# 0273_GPU_STRAPS-2.net
KiCad netlist of a schematic drawn in Altium Designer
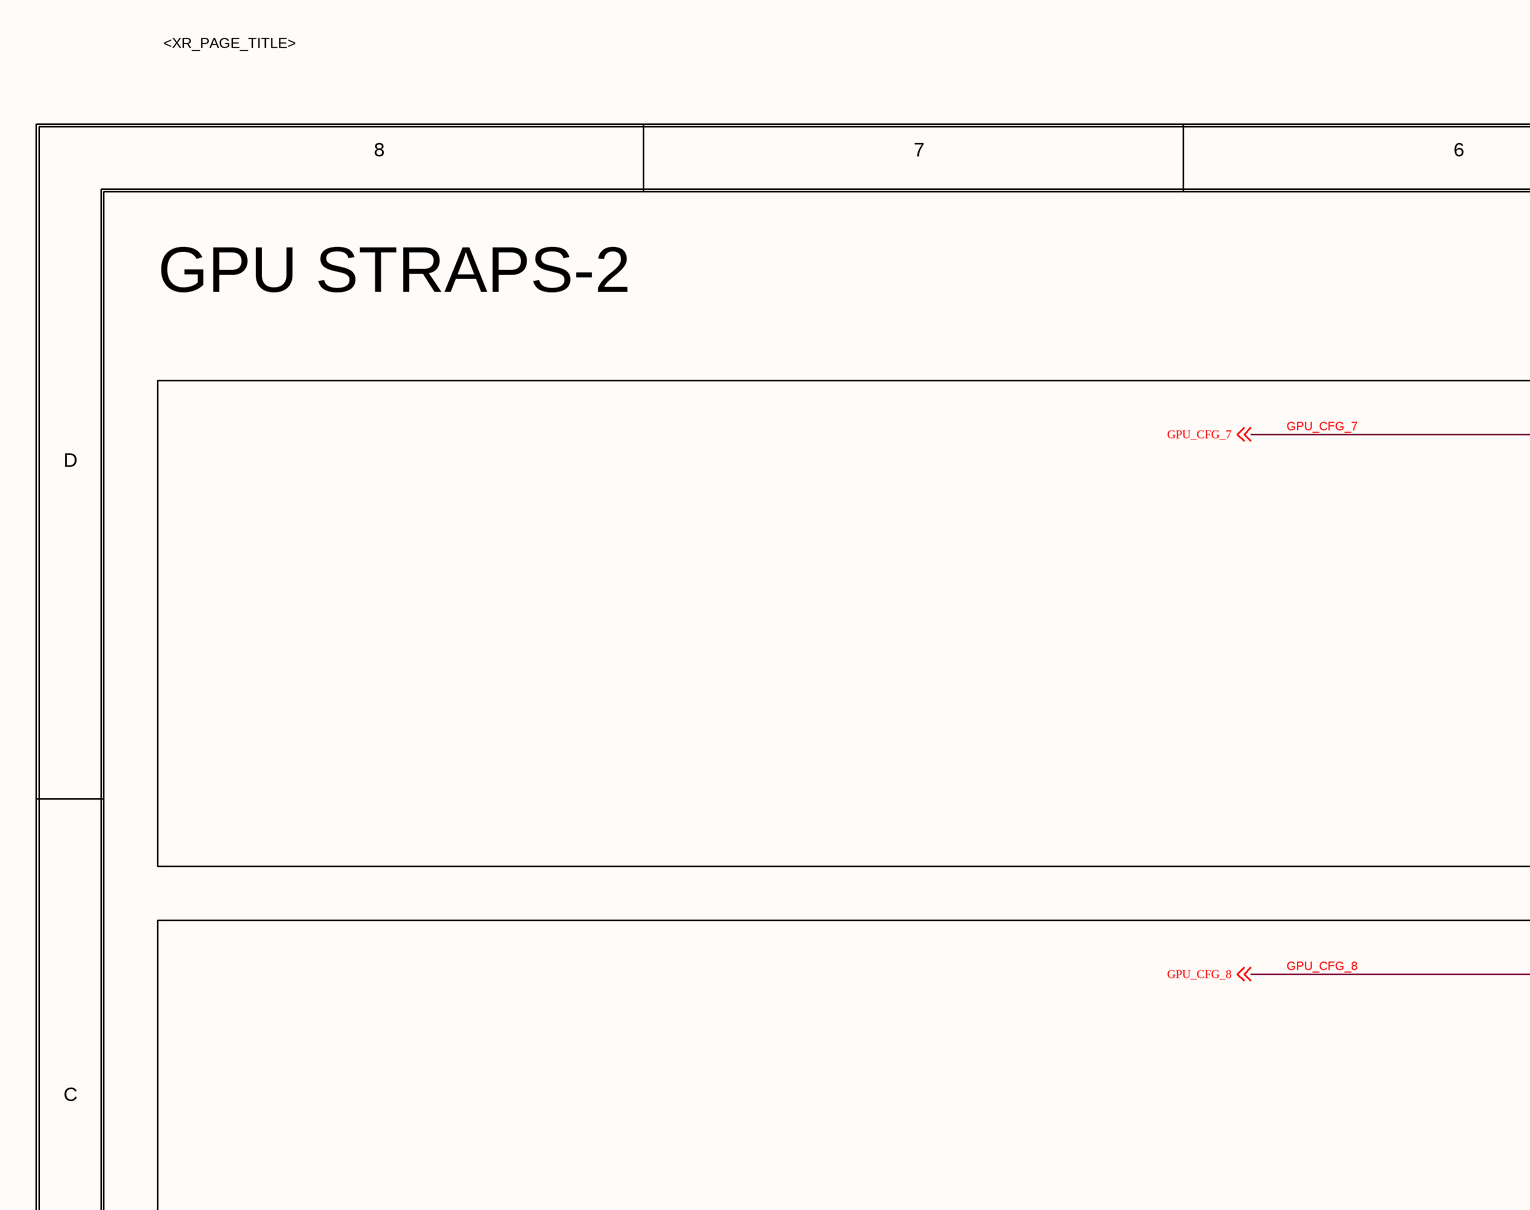
[diagram p0: 0273_GPU STRAPS-2.SchDoc, top left]
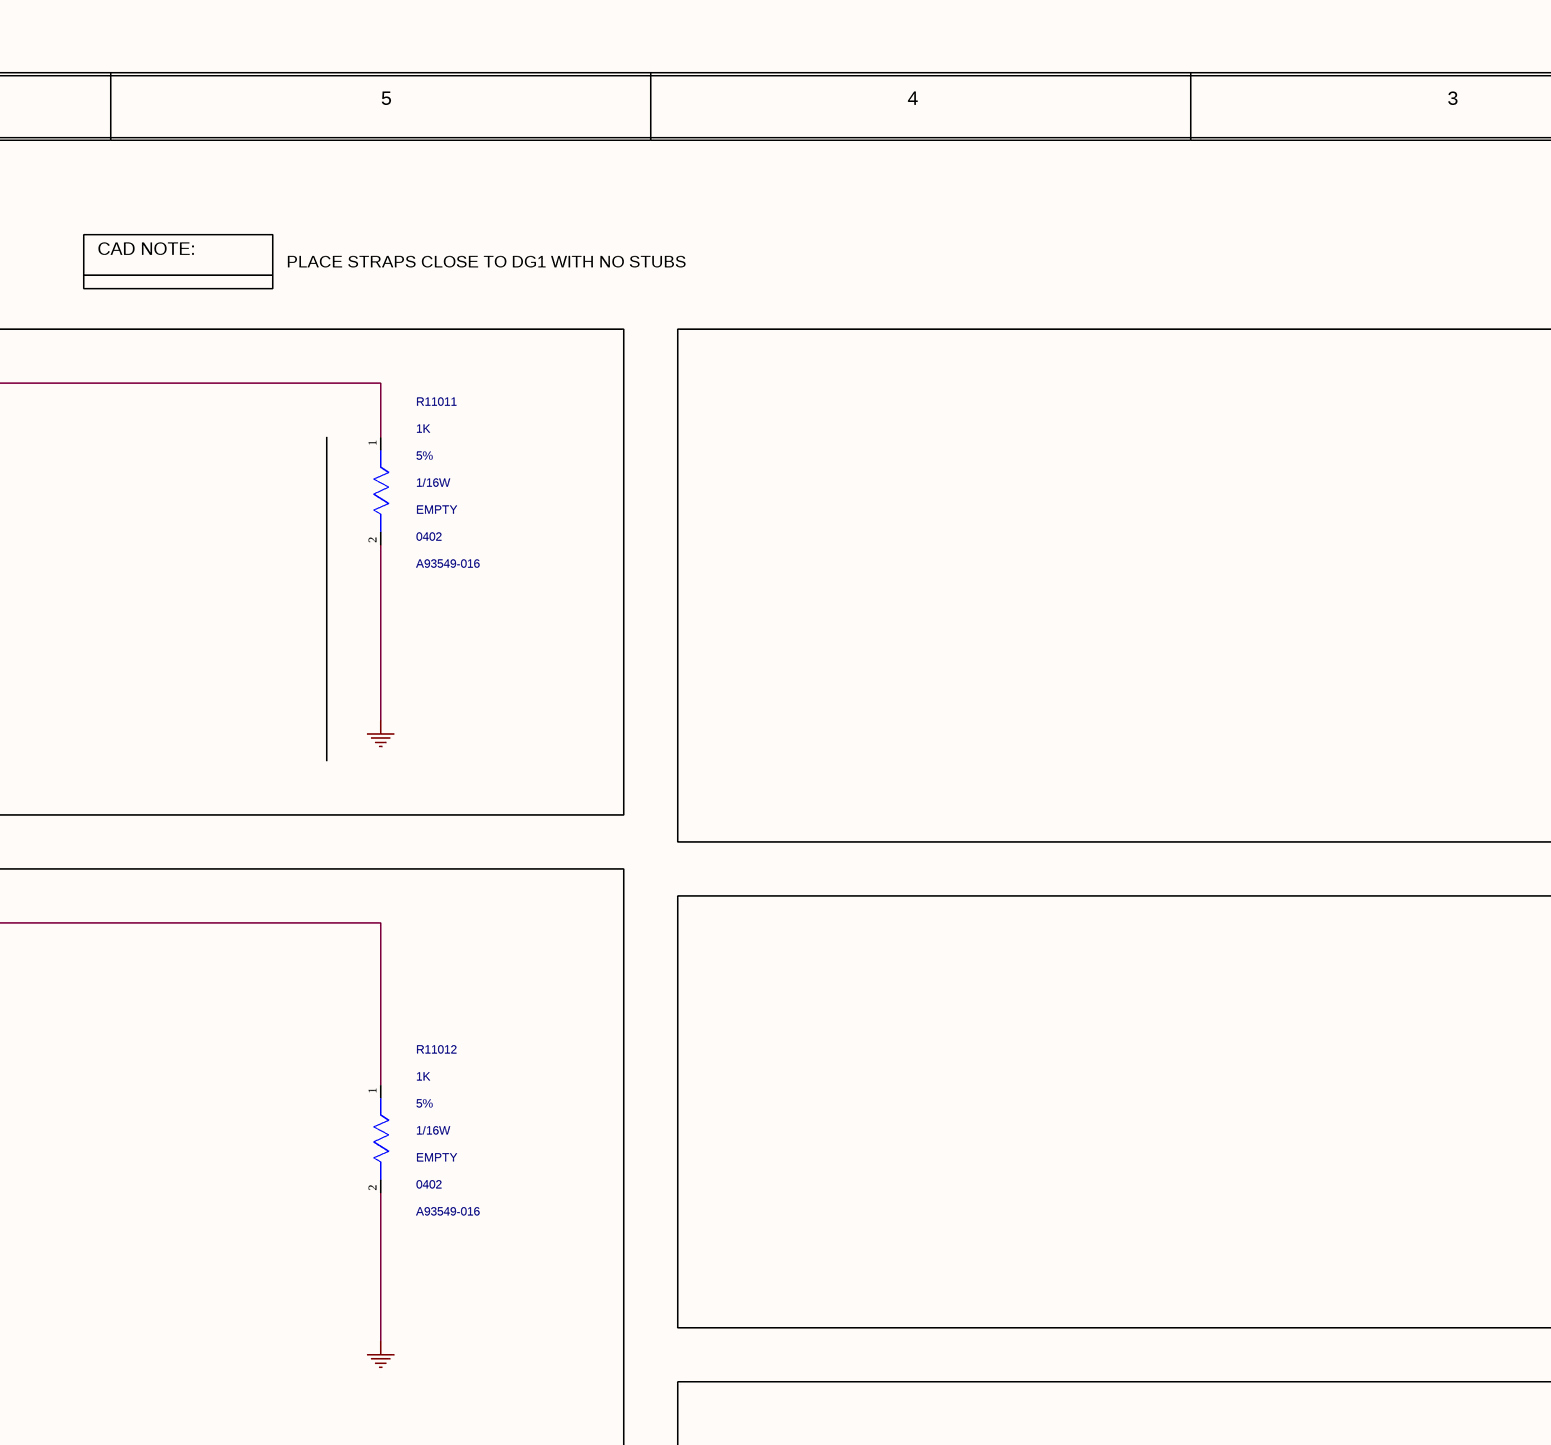
[diagram p1: 0273_GPU STRAPS-2.SchDoc, top middle]
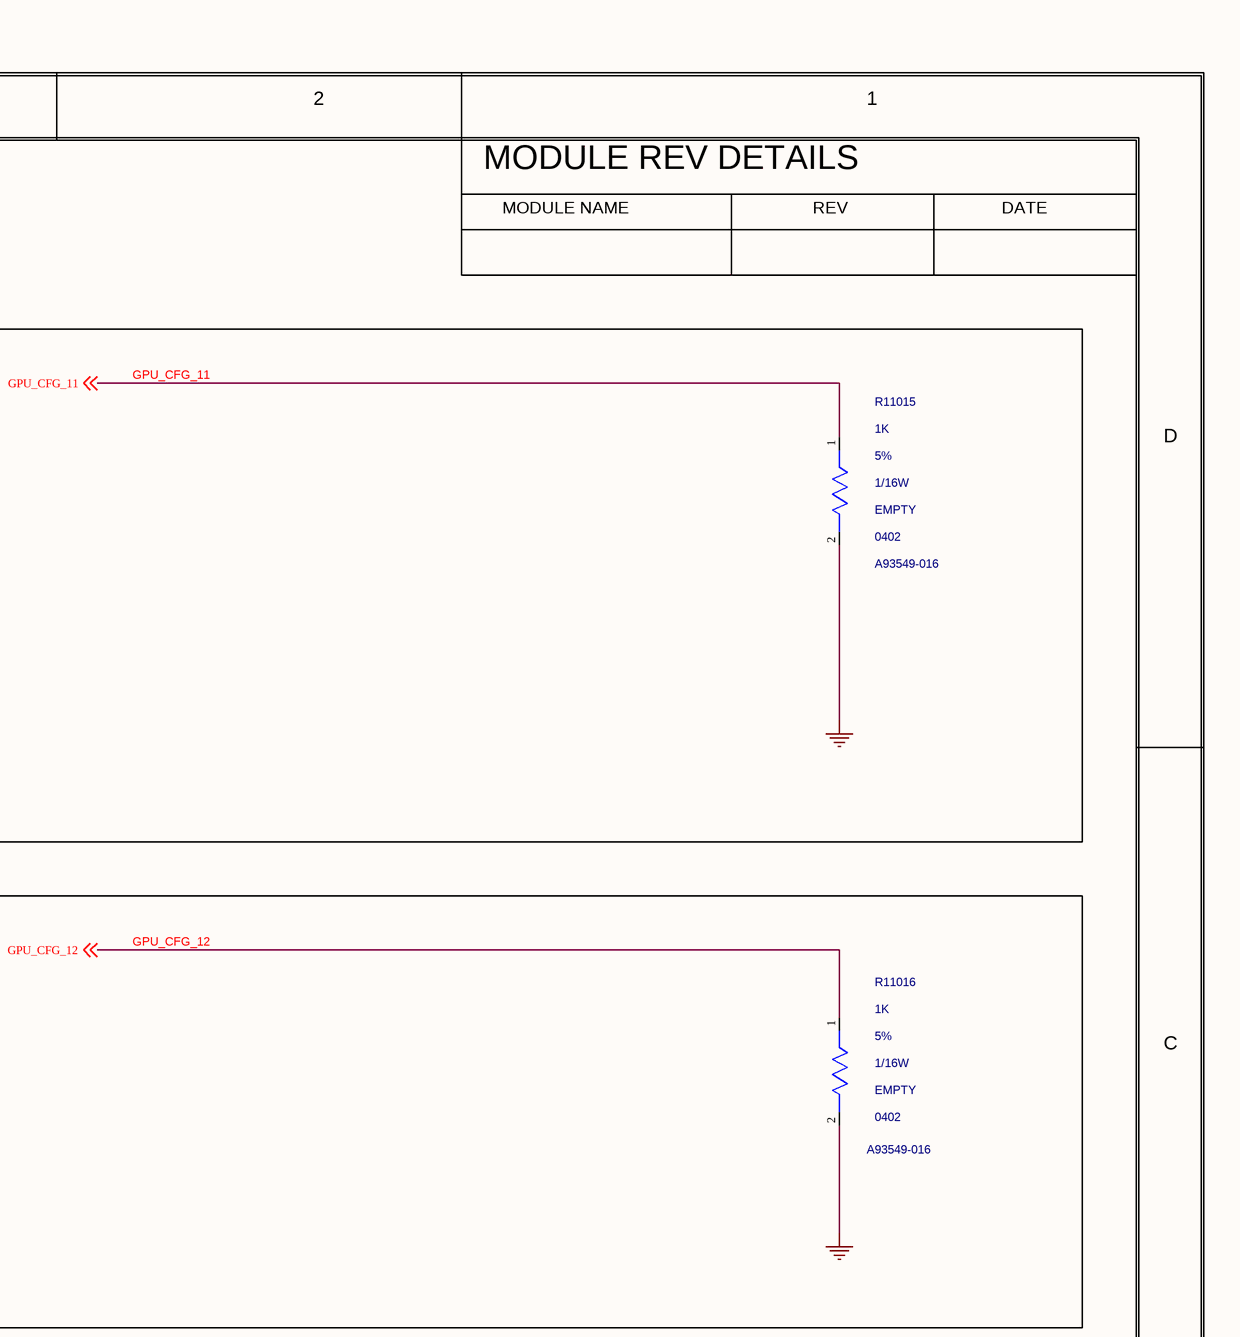
[diagram p2: 0273_GPU STRAPS-2.SchDoc, top right]
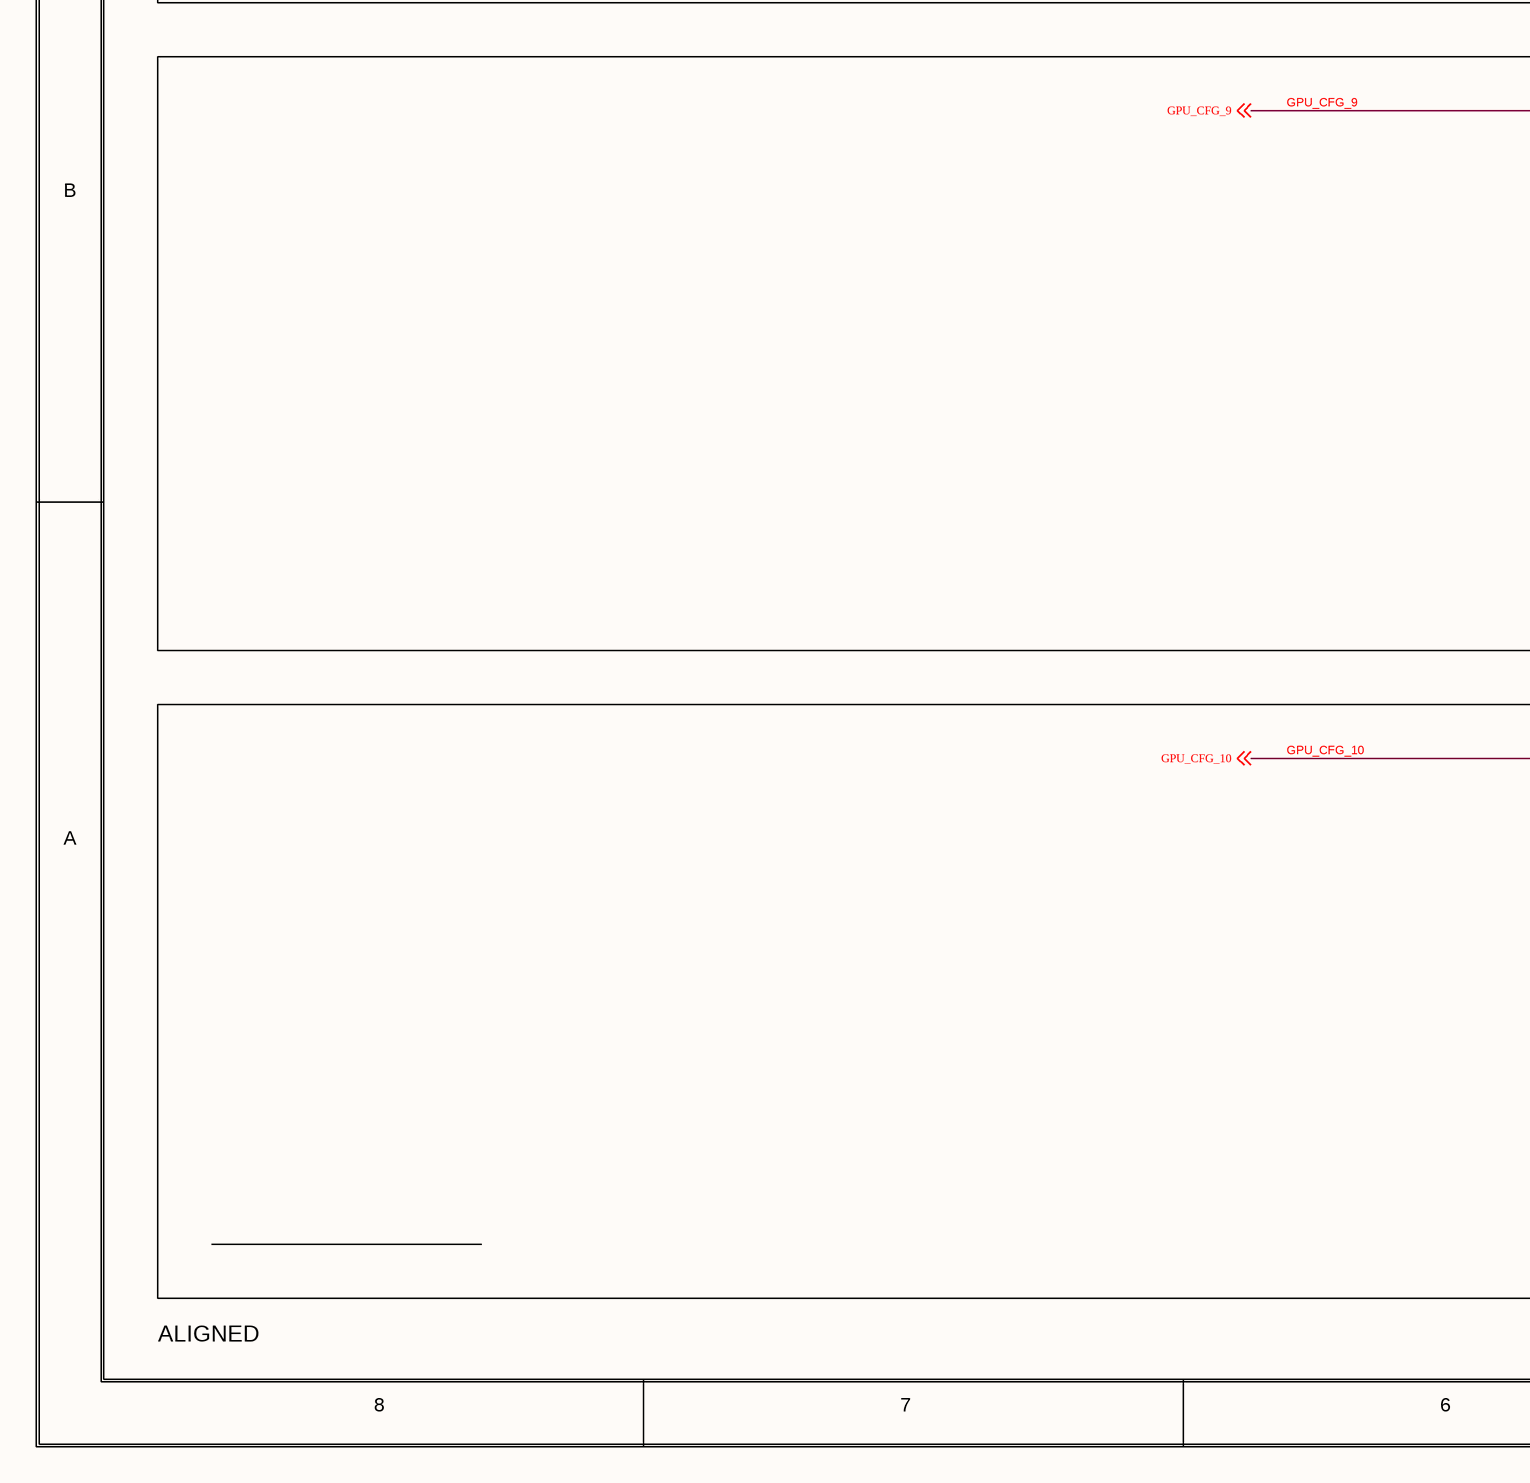
[diagram p3: 0273_GPU STRAPS-2.SchDoc, bottom left]
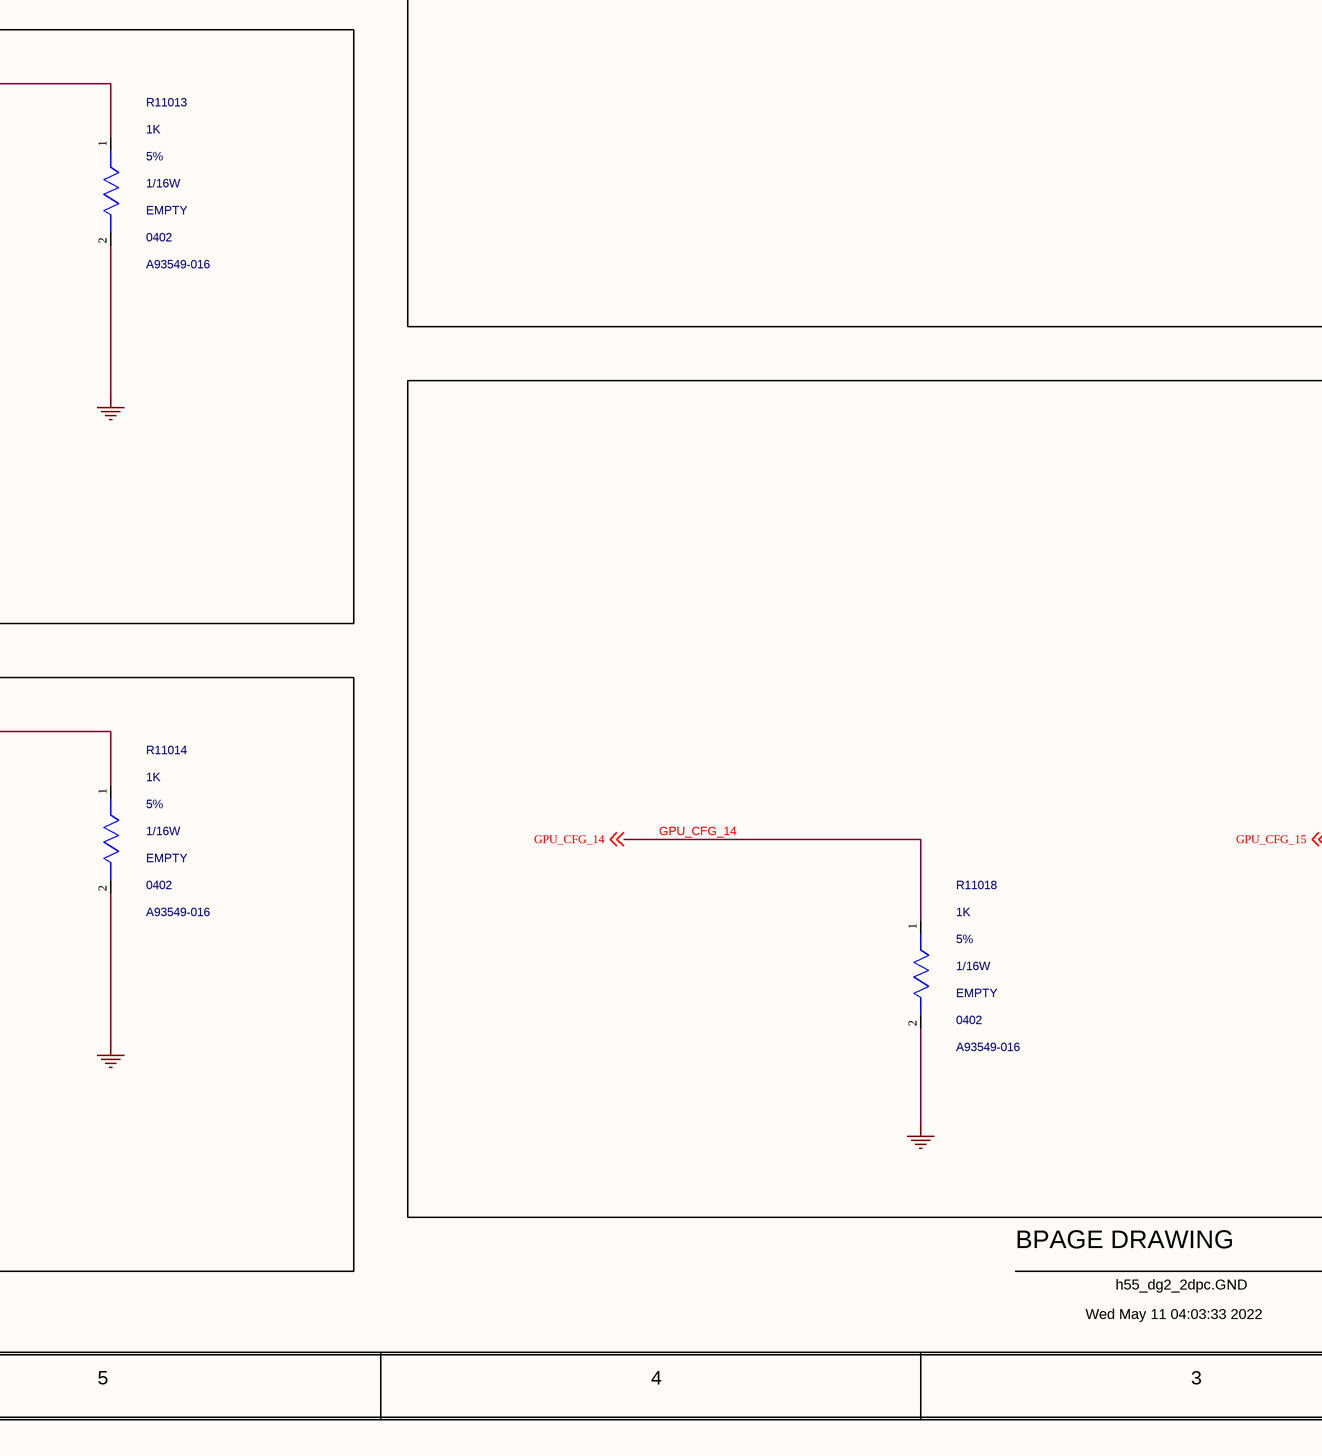
[diagram p4: 0273_GPU STRAPS-2.SchDoc, bottom middle]
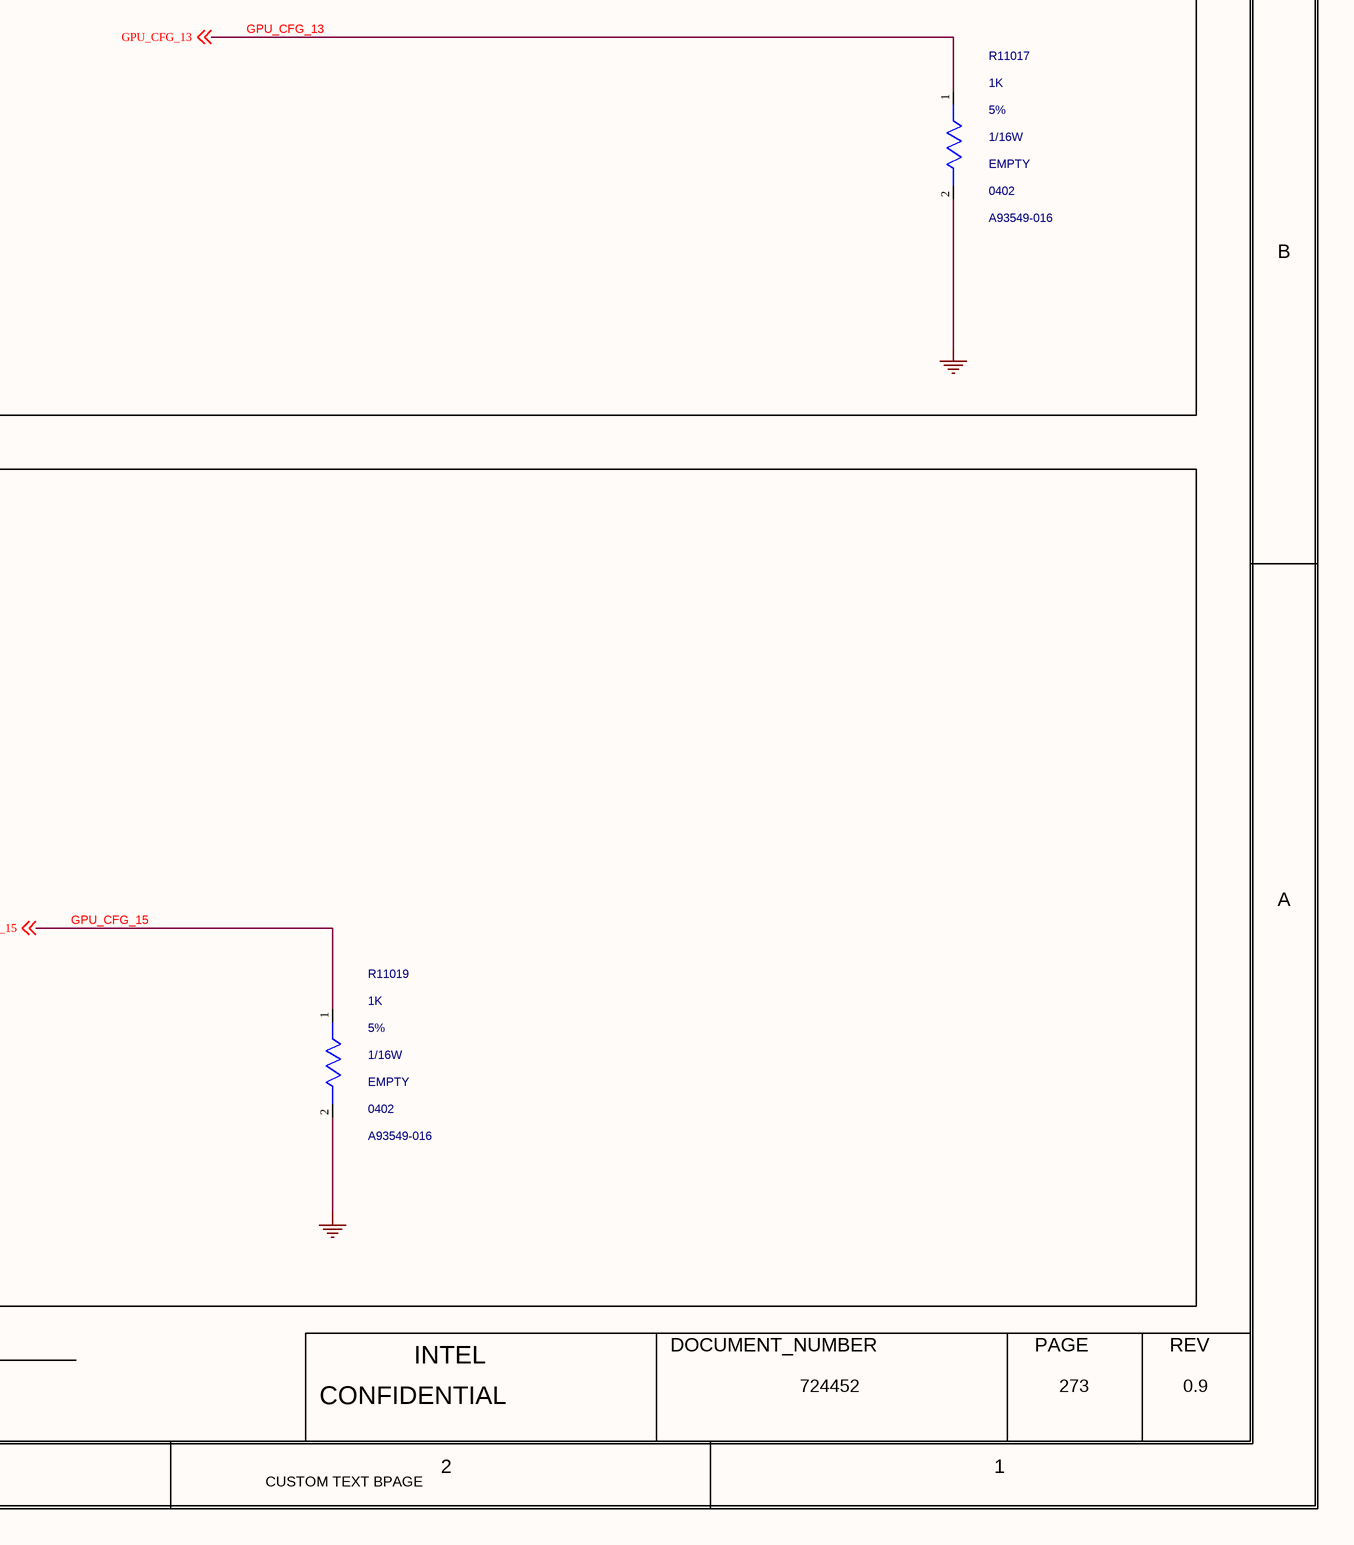
[diagram p5: 0273_GPU STRAPS-2.SchDoc, bottom right]

(export (version "E")
  (design (tool "Eeschema 10.0.6"))
  (components
    (comp (ref "R11011")
      (value "1K")
      (footprint "SMR0402IA")
      (fields
        (field (name "MATERIAL") "EMPTY")
        (field (name "PACK_TYPE") "0402")
        (field (name "PART_NUMBER") "A93549-016")
        (field (name "TOLERANCE") "5%")
        (field (name "WATTAGE") "1/16W")
      )
      (libsource (lib "*") (part "RES"))
    )
    (comp (ref "R11012")
      (value "1K")
      (footprint "SMR0402IA")
      (fields
        (field (name "MATERIAL") "EMPTY")
        (field (name "PACK_TYPE") "0402")
        (field (name "PART_NUMBER") "A93549-016")
        (field (name "TOLERANCE") "5%")
        (field (name "WATTAGE") "1/16W")
      )
      (libsource (lib "*") (part "RES"))
    )
    (comp (ref "R11013")
      (value "1K")
      (footprint "SMR0402IA")
      (fields
        (field (name "MATERIAL") "EMPTY")
        (field (name "PACK_TYPE") "0402")
        (field (name "PART_NUMBER") "A93549-016")
        (field (name "TOLERANCE") "5%")
        (field (name "WATTAGE") "1/16W")
      )
      (libsource (lib "*") (part "RES"))
    )
    (comp (ref "R11014")
      (value "1K")
      (footprint "SMR0402IA")
      (fields
        (field (name "MATERIAL") "EMPTY")
        (field (name "PACK_TYPE") "0402")
        (field (name "PART_NUMBER") "A93549-016")
        (field (name "TOLERANCE") "5%")
        (field (name "WATTAGE") "1/16W")
      )
      (libsource (lib "*") (part "RES"))
    )
    (comp (ref "R11015")
      (value "1K")
      (footprint "SMR0402IA")
      (fields
        (field (name "MATERIAL") "EMPTY")
        (field (name "PACK_TYPE") "0402")
        (field (name "PART_NUMBER") "A93549-016")
        (field (name "TOLERANCE") "5%")
        (field (name "WATTAGE") "1/16W")
      )
      (libsource (lib "*") (part "RES"))
    )
    (comp (ref "R11016")
      (value "1K")
      (footprint "SMR0402IA")
      (fields
        (field (name "MATERIAL") "EMPTY")
        (field (name "PACK_TYPE") "0402")
        (field (name "PART_NUMBER") "A93549-016")
        (field (name "TOLERANCE") "5%")
        (field (name "WATTAGE") "1/16W")
      )
      (libsource (lib "*") (part "RES"))
    )
    (comp (ref "R11017")
      (value "1K")
      (footprint "SMR0402IA")
      (fields
        (field (name "MATERIAL") "EMPTY")
        (field (name "PACK_TYPE") "0402")
        (field (name "PART_NUMBER") "A93549-016")
        (field (name "TOLERANCE") "5%")
        (field (name "WATTAGE") "1/16W")
      )
      (libsource (lib "*") (part "RES"))
    )
    (comp (ref "R11018")
      (value "1K")
      (footprint "SMR0402IA")
      (fields
        (field (name "MATERIAL") "EMPTY")
        (field (name "PACK_TYPE") "0402")
        (field (name "PART_NUMBER") "A93549-016")
        (field (name "TOLERANCE") "5%")
        (field (name "WATTAGE") "1/16W")
      )
      (libsource (lib "*") (part "RES"))
    )
    (comp (ref "R11019")
      (value "1K")
      (footprint "SMR0402IA")
      (fields
        (field (name "MATERIAL") "EMPTY")
        (field (name "PACK_TYPE") "0402")
        (field (name "PART_NUMBER") "A93549-016")
        (field (name "TOLERANCE") "5%")
        (field (name "WATTAGE") "1/16W")
      )
      (libsource (lib "*") (part "RES"))
    )
  )
  (nets
    (net (code "1") (name "GND") (class "Default")
      (node (ref "R11011") (pin "2") (pinfunction "B_2") (pintype "bidirectional"))
      (node (ref "R11012") (pin "2") (pinfunction "B_2") (pintype "bidirectional"))
      (node (ref "R11013") (pin "2") (pinfunction "B_2") (pintype "bidirectional"))
      (node (ref "R11014") (pin "2") (pinfunction "B_2") (pintype "bidirectional"))
      (node (ref "R11015") (pin "2") (pinfunction "B_2") (pintype "bidirectional"))
      (node (ref "R11016") (pin "2") (pinfunction "B_2") (pintype "bidirectional"))
      (node (ref "R11017") (pin "2") (pinfunction "B_2") (pintype "bidirectional"))
      (node (ref "R11018") (pin "2") (pinfunction "B_2") (pintype "bidirectional"))
      (node (ref "R11019") (pin "2") (pinfunction "B_2") (pintype "bidirectional"))
    )
    (net (code "2") (name "GPU_CFG_7") (class "Default")
      (node (ref "R11011") (pin "1") (pinfunction "A_1") (pintype "bidirectional"))
    )
    (net (code "3") (name "GPU_CFG_8") (class "Default")
      (node (ref "R11012") (pin "1") (pinfunction "A_1") (pintype "bidirectional"))
    )
    (net (code "4") (name "GPU_CFG_9") (class "Default")
      (node (ref "R11013") (pin "1") (pinfunction "A_1") (pintype "bidirectional"))
    )
    (net (code "5") (name "GPU_CFG_10") (class "Default")
      (node (ref "R11014") (pin "1") (pinfunction "A_1") (pintype "bidirectional"))
    )
    (net (code "6") (name "GPU_CFG_11") (class "Default")
      (node (ref "R11015") (pin "1") (pinfunction "A_1") (pintype "bidirectional"))
    )
    (net (code "7") (name "GPU_CFG_12") (class "Default")
      (node (ref "R11016") (pin "1") (pinfunction "A_1") (pintype "bidirectional"))
    )
    (net (code "8") (name "GPU_CFG_13") (class "Default")
      (node (ref "R11017") (pin "1") (pinfunction "A_1") (pintype "bidirectional"))
    )
    (net (code "9") (name "GPU_CFG_14") (class "Default")
      (node (ref "R11018") (pin "1") (pinfunction "A_1") (pintype "bidirectional"))
    )
    (net (code "10") (name "GPU_CFG_15") (class "Default")
      (node (ref "R11019") (pin "1") (pinfunction "A_1") (pintype "bidirectional"))
    )
  )
)
